# 74595.net
KiCad netlist of a schematic drawn in EAGLE
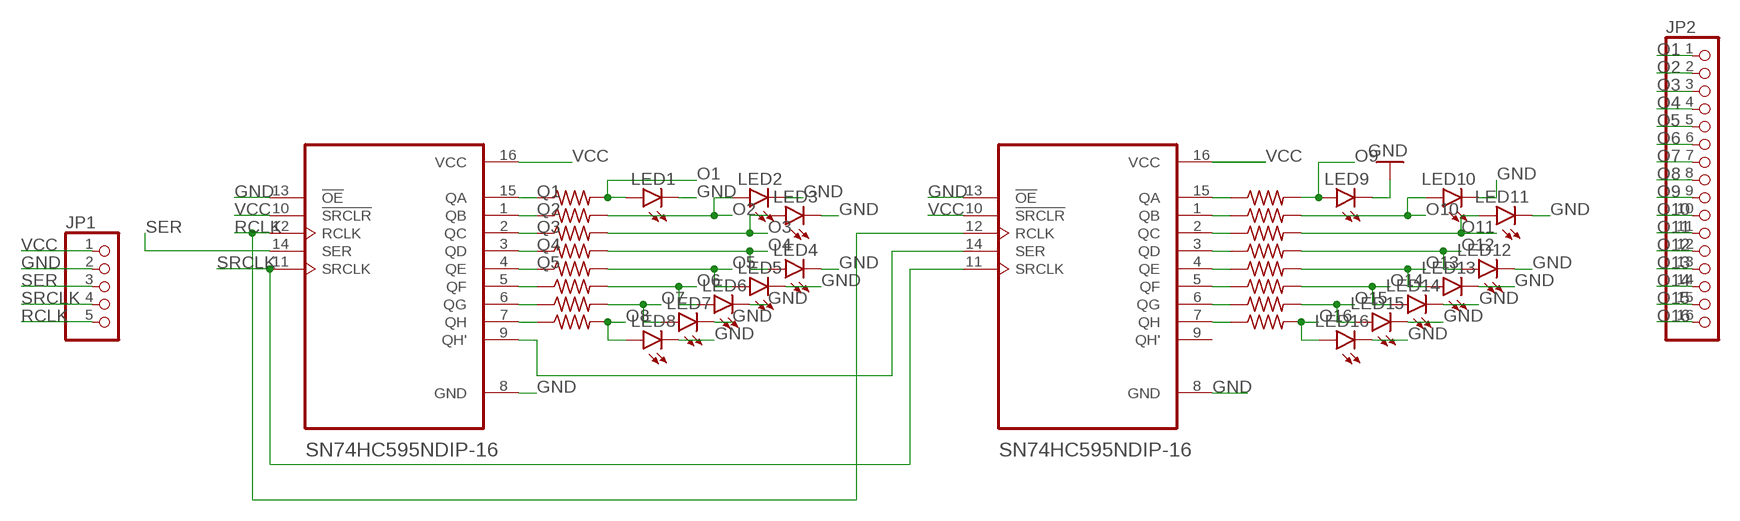
[diagram p0: schematic, sheet 1]

(export (version "E")
  (design (tool "Eeschema 10.0.6"))
  (components
    (comp (ref "JP1")
      (value "PINHD-1X5")
      (footprint "eagle-import:1X05")
      (libsource (lib "eagle-import") (part "PINHD-1X5"))
    )
    (comp (ref "JP2")
      (value "PINHD-1X16")
      (footprint "eagle-import:1X16")
      (libsource (lib "eagle-import") (part "PINHD-1X16"))
    )
    (comp (ref "LED1")
      (value "LEDCHIPLED_0805")
      (footprint "eagle-import:CHIPLED_0805")
      (libsource (lib "eagle-import") (part "LEDCHIPLED_0805"))
    )
    (comp (ref "LED2")
      (value "LEDCHIPLED_0805")
      (footprint "eagle-import:CHIPLED_0805")
      (libsource (lib "eagle-import") (part "LEDCHIPLED_0805"))
    )
    (comp (ref "LED3")
      (value "LEDCHIPLED_0805")
      (footprint "eagle-import:CHIPLED_0805")
      (libsource (lib "eagle-import") (part "LEDCHIPLED_0805"))
    )
    (comp (ref "LED4")
      (value "LEDCHIPLED_0805")
      (footprint "eagle-import:CHIPLED_0805")
      (libsource (lib "eagle-import") (part "LEDCHIPLED_0805"))
    )
    (comp (ref "LED5")
      (value "LEDCHIPLED_0805")
      (footprint "eagle-import:CHIPLED_0805")
      (libsource (lib "eagle-import") (part "LEDCHIPLED_0805"))
    )
    (comp (ref "LED6")
      (value "LEDCHIPLED_0805")
      (footprint "eagle-import:CHIPLED_0805")
      (libsource (lib "eagle-import") (part "LEDCHIPLED_0805"))
    )
    (comp (ref "LED7")
      (value "LEDCHIPLED_0805")
      (footprint "eagle-import:CHIPLED_0805")
      (libsource (lib "eagle-import") (part "LEDCHIPLED_0805"))
    )
    (comp (ref "LED8")
      (value "LEDCHIPLED_0805")
      (footprint "eagle-import:CHIPLED_0805")
      (libsource (lib "eagle-import") (part "LEDCHIPLED_0805"))
    )
    (comp (ref "LED9")
      (value "LEDCHIPLED_0805")
      (footprint "eagle-import:CHIPLED_0805")
      (libsource (lib "eagle-import") (part "LEDCHIPLED_0805"))
    )
    (comp (ref "LED10")
      (value "LEDCHIPLED_0805")
      (footprint "eagle-import:CHIPLED_0805")
      (libsource (lib "eagle-import") (part "LEDCHIPLED_0805"))
    )
    (comp (ref "LED11")
      (value "LEDCHIPLED_0805")
      (footprint "eagle-import:CHIPLED_0805")
      (libsource (lib "eagle-import") (part "LEDCHIPLED_0805"))
    )
    (comp (ref "LED12")
      (value "LEDCHIPLED_0805")
      (footprint "eagle-import:CHIPLED_0805")
      (libsource (lib "eagle-import") (part "LEDCHIPLED_0805"))
    )
    (comp (ref "LED13")
      (value "LEDCHIPLED_0805")
      (footprint "eagle-import:CHIPLED_0805")
      (libsource (lib "eagle-import") (part "LEDCHIPLED_0805"))
    )
    (comp (ref "LED14")
      (value "LEDCHIPLED_0805")
      (footprint "eagle-import:CHIPLED_0805")
      (libsource (lib "eagle-import") (part "LEDCHIPLED_0805"))
    )
    (comp (ref "LED15")
      (value "LEDCHIPLED_0805")
      (footprint "eagle-import:CHIPLED_0805")
      (libsource (lib "eagle-import") (part "LEDCHIPLED_0805"))
    )
    (comp (ref "LED16")
      (value "LEDCHIPLED_0805")
      (footprint "eagle-import:CHIPLED_0805")
      (libsource (lib "eagle-import") (part "LEDCHIPLED_0805"))
    )
    (comp (ref "R1")
      (value "R-US_R0805")
      (footprint "eagle-import:R0805")
      (libsource (lib "eagle-import") (part "R-US_R0805"))
    )
    (comp (ref "R2")
      (value "R-US_R0805")
      (footprint "eagle-import:R0805")
      (libsource (lib "eagle-import") (part "R-US_R0805"))
    )
    (comp (ref "R3")
      (value "R-US_R0805")
      (footprint "eagle-import:R0805")
      (libsource (lib "eagle-import") (part "R-US_R0805"))
    )
    (comp (ref "R4")
      (value "R-US_R0805")
      (footprint "eagle-import:R0805")
      (libsource (lib "eagle-import") (part "R-US_R0805"))
    )
    (comp (ref "R5")
      (value "R-US_R0805")
      (footprint "eagle-import:R0805")
      (libsource (lib "eagle-import") (part "R-US_R0805"))
    )
    (comp (ref "R6")
      (value "R-US_R0805")
      (footprint "eagle-import:R0805")
      (libsource (lib "eagle-import") (part "R-US_R0805"))
    )
    (comp (ref "R7")
      (value "R-US_R0805")
      (footprint "eagle-import:R0805")
      (libsource (lib "eagle-import") (part "R-US_R0805"))
    )
    (comp (ref "R8")
      (value "R-US_R0805")
      (footprint "eagle-import:R0805")
      (libsource (lib "eagle-import") (part "R-US_R0805"))
    )
    (comp (ref "R9")
      (value "R-US_R0805")
      (footprint "eagle-import:R0805")
      (libsource (lib "eagle-import") (part "R-US_R0805"))
    )
    (comp (ref "R10")
      (value "R-US_R0805")
      (footprint "eagle-import:R0805")
      (libsource (lib "eagle-import") (part "R-US_R0805"))
    )
    (comp (ref "R11")
      (value "R-US_R0805")
      (footprint "eagle-import:R0805")
      (libsource (lib "eagle-import") (part "R-US_R0805"))
    )
    (comp (ref "R12")
      (value "R-US_R0805")
      (footprint "eagle-import:R0805")
      (libsource (lib "eagle-import") (part "R-US_R0805"))
    )
    (comp (ref "R13")
      (value "R-US_R0805")
      (footprint "eagle-import:R0805")
      (libsource (lib "eagle-import") (part "R-US_R0805"))
    )
    (comp (ref "R14")
      (value "R-US_R0805")
      (footprint "eagle-import:R0805")
      (libsource (lib "eagle-import") (part "R-US_R0805"))
    )
    (comp (ref "R15")
      (value "R-US_R0805")
      (footprint "eagle-import:R0805")
      (libsource (lib "eagle-import") (part "R-US_R0805"))
    )
    (comp (ref "R16")
      (value "R-US_R0805")
      (footprint "eagle-import:R0805")
      (libsource (lib "eagle-import") (part "R-US_R0805"))
    )
    (comp (ref "U1")
      (value "SN74HC595NDIP-16")
      (footprint "eagle-import:DIP794W45P254L1969H508Q16")
      (fields (field (name "MF") "Texas Instruments") (field (name "MP") "SN74HC595N"))
      (libsource (lib "eagle-import") (part "SN74HC595NDIP-16"))
    )
    (comp (ref "U2")
      (value "SN74HC595NDIP-16")
      (footprint "eagle-import:DIP794W45P254L1969H508Q16")
      (fields (field (name "MF") "Texas Instruments") (field (name "MP") "SN74HC595N"))
      (libsource (lib "eagle-import") (part "SN74HC595NDIP-16"))
    )
  )
  (nets
    (net (code "1") (name "/O1") (class "Default")
      (node (ref "JP2") (pin "1") (pinfunction "1_1") (pintype "passive"))
      (node (ref "LED1") (pin "A") (pinfunction "A_A") (pintype "passive"))
      (node (ref "R1") (pin "2") (pinfunction "2_2") (pintype "passive"))
    )
    (net (code "2") (name "/O2") (class "Default")
      (node (ref "JP2") (pin "2") (pinfunction "2_2") (pintype "passive"))
      (node (ref "LED2") (pin "A") (pinfunction "A_A") (pintype "passive"))
      (node (ref "R2") (pin "2") (pinfunction "2_2") (pintype "passive"))
    )
    (net (code "3") (name "/O3") (class "Default")
      (node (ref "JP2") (pin "3") (pinfunction "3_3") (pintype "passive"))
      (node (ref "LED3") (pin "A") (pinfunction "A_A") (pintype "passive"))
      (node (ref "R3") (pin "2") (pinfunction "2_2") (pintype "passive"))
    )
    (net (code "4") (name "/O4") (class "Default")
      (node (ref "JP2") (pin "4") (pinfunction "4_4") (pintype "passive"))
      (node (ref "LED4") (pin "A") (pinfunction "A_A") (pintype "passive"))
      (node (ref "R4") (pin "2") (pinfunction "2_2") (pintype "passive"))
    )
    (net (code "5") (name "/O5") (class "Default")
      (node (ref "JP2") (pin "5") (pinfunction "5_5") (pintype "passive"))
      (node (ref "LED5") (pin "A") (pinfunction "A_A") (pintype "passive"))
      (node (ref "R5") (pin "2") (pinfunction "2_2") (pintype "passive"))
    )
    (net (code "6") (name "/O6") (class "Default")
      (node (ref "JP2") (pin "6") (pinfunction "6_6") (pintype "passive"))
      (node (ref "LED6") (pin "A") (pinfunction "A_A") (pintype "passive"))
      (node (ref "R6") (pin "2") (pinfunction "2_2") (pintype "passive"))
    )
    (net (code "7") (name "/O7") (class "Default")
      (node (ref "JP2") (pin "7") (pinfunction "7_7") (pintype "passive"))
      (node (ref "LED7") (pin "A") (pinfunction "A_A") (pintype "passive"))
      (node (ref "R8") (pin "2") (pinfunction "2_2") (pintype "passive"))
    )
    (net (code "8") (name "/O8") (class "Default")
      (node (ref "JP2") (pin "8") (pinfunction "8_8") (pintype "passive"))
      (node (ref "LED8") (pin "A") (pinfunction "A_A") (pintype "passive"))
      (node (ref "R9") (pin "2") (pinfunction "2_2") (pintype "passive"))
    )
    (net (code "9") (name "/O9") (class "Default")
      (node (ref "JP2") (pin "9") (pinfunction "9_9") (pintype "passive"))
      (node (ref "LED9") (pin "A") (pinfunction "A_A") (pintype "passive"))
      (node (ref "R7") (pin "2") (pinfunction "2_2") (pintype "passive"))
    )
    (net (code "10") (name "/O10") (class "Default")
      (node (ref "JP2") (pin "10") (pinfunction "10_10") (pintype "passive"))
      (node (ref "LED10") (pin "A") (pinfunction "A_A") (pintype "passive"))
      (node (ref "R10") (pin "2") (pinfunction "2_2") (pintype "passive"))
    )
    (net (code "11") (name "/O11") (class "Default")
      (node (ref "JP2") (pin "11") (pinfunction "11_11") (pintype "passive"))
      (node (ref "LED11") (pin "A") (pinfunction "A_A") (pintype "passive"))
      (node (ref "R11") (pin "2") (pinfunction "2_2") (pintype "passive"))
    )
    (net (code "12") (name "/O12") (class "Default")
      (node (ref "JP2") (pin "12") (pinfunction "12_12") (pintype "passive"))
      (node (ref "LED12") (pin "A") (pinfunction "A_A") (pintype "passive"))
      (node (ref "R12") (pin "2") (pinfunction "2_2") (pintype "passive"))
    )
    (net (code "13") (name "/O13") (class "Default")
      (node (ref "JP2") (pin "13") (pinfunction "13_13") (pintype "passive"))
      (node (ref "LED13") (pin "A") (pinfunction "A_A") (pintype "passive"))
      (node (ref "R13") (pin "2") (pinfunction "2_2") (pintype "passive"))
    )
    (net (code "14") (name "/O14") (class "Default")
      (node (ref "JP2") (pin "14") (pinfunction "14_14") (pintype "passive"))
      (node (ref "LED14") (pin "A") (pinfunction "A_A") (pintype "passive"))
      (node (ref "R14") (pin "2") (pinfunction "2_2") (pintype "passive"))
    )
    (net (code "15") (name "/O15") (class "Default")
      (node (ref "JP2") (pin "15") (pinfunction "15_15") (pintype "passive"))
      (node (ref "LED15") (pin "A") (pinfunction "A_A") (pintype "passive"))
      (node (ref "R15") (pin "2") (pinfunction "2_2") (pintype "passive"))
    )
    (net (code "16") (name "/O16") (class "Default")
      (node (ref "JP2") (pin "16") (pinfunction "16_16") (pintype "passive"))
      (node (ref "LED16") (pin "A") (pinfunction "A_A") (pintype "passive"))
      (node (ref "R16") (pin "2") (pinfunction "2_2") (pintype "passive"))
    )
    (net (code "17") (name "/Q1") (class "Default")
      (node (ref "R1") (pin "1") (pinfunction "1_1") (pintype "passive"))
      (node (ref "U1") (pin "15") (pinfunction "QA_15") (pintype "output"))
    )
    (net (code "18") (name "/Q2") (class "Default")
      (node (ref "R2") (pin "1") (pinfunction "1_1") (pintype "passive"))
      (node (ref "U1") (pin "1") (pinfunction "QB_1") (pintype "output"))
    )
    (net (code "19") (name "/Q3") (class "Default")
      (node (ref "R3") (pin "1") (pinfunction "1_1") (pintype "passive"))
      (node (ref "U1") (pin "2") (pinfunction "QC_2") (pintype "output"))
    )
    (net (code "20") (name "/Q4") (class "Default")
      (node (ref "R4") (pin "1") (pinfunction "1_1") (pintype "passive"))
      (node (ref "U1") (pin "3") (pinfunction "QD_3") (pintype "output"))
    )
    (net (code "21") (name "/Q5") (class "Default")
      (node (ref "R5") (pin "1") (pinfunction "1_1") (pintype "passive"))
      (node (ref "U1") (pin "4") (pinfunction "QE_4") (pintype "output"))
    )
    (net (code "22") (name "/RCLK") (class "Default")
      (node (ref "JP1") (pin "5") (pinfunction "5_5") (pintype "passive"))
      (node (ref "U1") (pin "12") (pinfunction "RCLK_12") (pintype "input"))
      (node (ref "U2") (pin "12") (pinfunction "RCLK_12") (pintype "input"))
    )
    (net (code "23") (name "/SER") (class "Default")
      (node (ref "JP1") (pin "3") (pinfunction "3_3") (pintype "passive"))
      (node (ref "U1") (pin "14") (pinfunction "SER_14") (pintype "input"))
    )
    (net (code "24") (name "/SRCLK") (class "Default")
      (node (ref "JP1") (pin "4") (pinfunction "4_4") (pintype "passive"))
      (node (ref "U1") (pin "11") (pinfunction "SRCLK_11") (pintype "input"))
      (node (ref "U2") (pin "11") (pinfunction "SRCLK_11") (pintype "input"))
    )
    (net (code "25") (name "/VCC") (class "Default")
      (node (ref "JP1") (pin "1") (pinfunction "1_1") (pintype "passive"))
      (node (ref "U1") (pin "10") (pinfunction "~{SRCLR}_10") (pintype "input"))
      (node (ref "U1") (pin "16") (pinfunction "VCC_16") (pintype "power_in"))
      (node (ref "U2") (pin "10") (pinfunction "~{SRCLR}_10") (pintype "input"))
      (node (ref "U2") (pin "16") (pinfunction "VCC_16") (pintype "power_in"))
    )
    (net (code "26") (name "GND") (class "Default")
      (node (ref "JP1") (pin "2") (pinfunction "2_2") (pintype "passive"))
      (node (ref "LED1") (pin "C") (pinfunction "C_C") (pintype "passive"))
      (node (ref "LED10") (pin "C") (pinfunction "C_C") (pintype "passive"))
      (node (ref "LED11") (pin "C") (pinfunction "C_C") (pintype "passive"))
      (node (ref "LED12") (pin "C") (pinfunction "C_C") (pintype "passive"))
      (node (ref "LED13") (pin "C") (pinfunction "C_C") (pintype "passive"))
      (node (ref "LED14") (pin "C") (pinfunction "C_C") (pintype "passive"))
      (node (ref "LED15") (pin "C") (pinfunction "C_C") (pintype "passive"))
      (node (ref "LED16") (pin "C") (pinfunction "C_C") (pintype "passive"))
      (node (ref "LED2") (pin "C") (pinfunction "C_C") (pintype "passive"))
      (node (ref "LED3") (pin "C") (pinfunction "C_C") (pintype "passive"))
      (node (ref "LED4") (pin "C") (pinfunction "C_C") (pintype "passive"))
      (node (ref "LED5") (pin "C") (pinfunction "C_C") (pintype "passive"))
      (node (ref "LED6") (pin "C") (pinfunction "C_C") (pintype "passive"))
      (node (ref "LED7") (pin "C") (pinfunction "C_C") (pintype "passive"))
      (node (ref "LED8") (pin "C") (pinfunction "C_C") (pintype "passive"))
      (node (ref "LED9") (pin "C") (pinfunction "C_C") (pintype "passive"))
      (node (ref "U1") (pin "13") (pinfunction "~{OE}_13") (pintype "input"))
      (node (ref "U1") (pin "8") (pinfunction "GND_8") (pintype "power_in"))
      (node (ref "U2") (pin "13") (pinfunction "~{OE}_13") (pintype "input"))
      (node (ref "U2") (pin "8") (pinfunction "GND_8") (pintype "power_in"))
    )
    (net (code "27") (name "Net-(U1-QF)") (class "Default")
      (node (ref "R6") (pin "1") (pinfunction "1_1") (pintype "passive"))
      (node (ref "U1") (pin "5") (pinfunction "QF_5") (pintype "output"))
    )
    (net (code "28") (name "Net-(U1-QG)") (class "Default")
      (node (ref "R8") (pin "1") (pinfunction "1_1") (pintype "passive"))
      (node (ref "U1") (pin "6") (pinfunction "QG_6") (pintype "output"))
    )
    (net (code "29") (name "Net-(U1-QH')") (class "Default")
      (node (ref "U1") (pin "9") (pinfunction "QH'_9") (pintype "output"))
      (node (ref "U2") (pin "14") (pinfunction "SER_14") (pintype "input"))
    )
    (net (code "30") (name "Net-(U1-QH)") (class "Default")
      (node (ref "R9") (pin "1") (pinfunction "1_1") (pintype "passive"))
      (node (ref "U1") (pin "7") (pinfunction "QH_7") (pintype "output"))
    )
    (net (code "31") (name "Net-(U2-QA)") (class "Default")
      (node (ref "R7") (pin "1") (pinfunction "1_1") (pintype "passive"))
      (node (ref "U2") (pin "15") (pinfunction "QA_15") (pintype "output"))
    )
    (net (code "32") (name "Net-(U2-QB)") (class "Default")
      (node (ref "R10") (pin "1") (pinfunction "1_1") (pintype "passive"))
      (node (ref "U2") (pin "1") (pinfunction "QB_1") (pintype "output"))
    )
    (net (code "33") (name "Net-(U2-QC)") (class "Default")
      (node (ref "R11") (pin "1") (pinfunction "1_1") (pintype "passive"))
      (node (ref "U2") (pin "2") (pinfunction "QC_2") (pintype "output"))
    )
    (net (code "34") (name "Net-(U2-QD)") (class "Default")
      (node (ref "R12") (pin "1") (pinfunction "1_1") (pintype "passive"))
      (node (ref "U2") (pin "3") (pinfunction "QD_3") (pintype "output"))
    )
    (net (code "35") (name "Net-(U2-QE)") (class "Default")
      (node (ref "R13") (pin "1") (pinfunction "1_1") (pintype "passive"))
      (node (ref "U2") (pin "4") (pinfunction "QE_4") (pintype "output"))
    )
    (net (code "36") (name "Net-(U2-QF)") (class "Default")
      (node (ref "R14") (pin "1") (pinfunction "1_1") (pintype "passive"))
      (node (ref "U2") (pin "5") (pinfunction "QF_5") (pintype "output"))
    )
    (net (code "37") (name "Net-(U2-QG)") (class "Default")
      (node (ref "R15") (pin "1") (pinfunction "1_1") (pintype "passive"))
      (node (ref "U2") (pin "6") (pinfunction "QG_6") (pintype "output"))
    )
    (net (code "38") (name "Net-(U2-QH)") (class "Default")
      (node (ref "R16") (pin "1") (pinfunction "1_1") (pintype "passive"))
      (node (ref "U2") (pin "7") (pinfunction "QH_7") (pintype "output"))
    )
    (net (code "39") (name "unconnected-(U2-QH'-Pad9)") (class "Default")
      (node (ref "U2") (pin "9") (pinfunction "QH'_9") (pintype "output"))
    )
  )
)
